# Buttons.net
KiCad netlist of a schematic drawn in Altium Designer
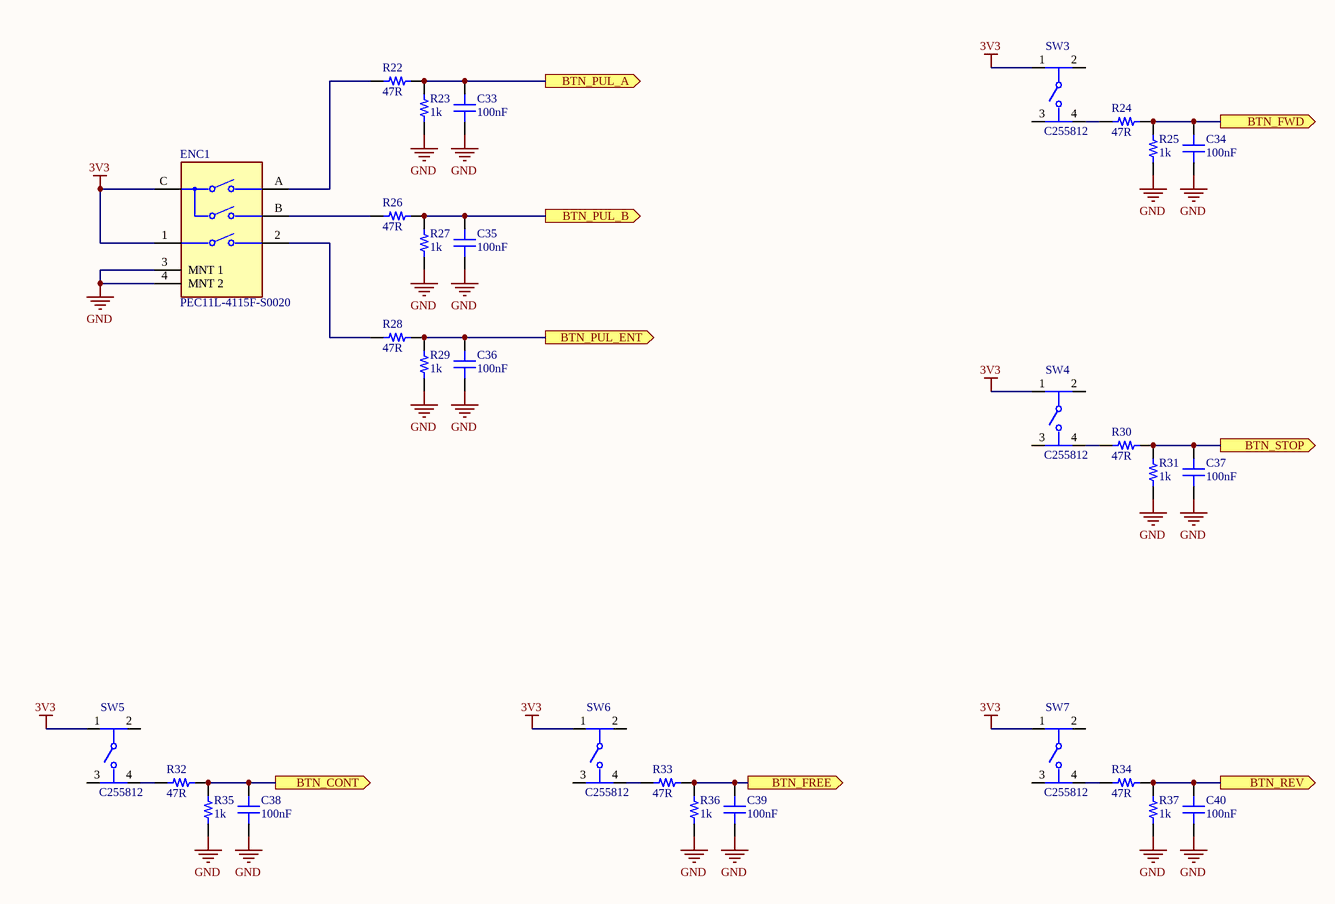
[diagram p0: Buttons.SchDoc]

(export (version "E")
  (design (tool "Eeschema 10.0.6"))
  (components
    (comp (ref "C33")
      (value "100nF")
      (footprint "CAP 0603_1608")
      (description "C14663")
      (fields
        (field (name "PART NUMBER") "250X14W223MV4T")
        (field (name "MANUFACTURER") "Johanson Dielectrics Inc.")
      )
      (libsource (lib "Celestial Altium Library - altium_library") (part "Capacitor"))
    )
    (comp (ref "C34")
      (value "100nF")
      (footprint "CAP 0603_1608")
      (description "C14663")
      (fields
        (field (name "PART NUMBER") "250X14W223MV4T")
        (field (name "MANUFACTURER") "Johanson Dielectrics Inc.")
      )
      (libsource (lib "Celestial Altium Library - altium_library") (part "Capacitor"))
    )
    (comp (ref "C35")
      (value "100nF")
      (footprint "CAP 0603_1608")
      (description "C14663")
      (fields
        (field (name "PART NUMBER") "250X14W223MV4T")
        (field (name "MANUFACTURER") "Johanson Dielectrics Inc.")
      )
      (libsource (lib "Celestial Altium Library - altium_library") (part "Capacitor"))
    )
    (comp (ref "C36")
      (value "100nF")
      (footprint "CAP 0603_1608")
      (description "C14663")
      (fields
        (field (name "PART NUMBER") "250X14W223MV4T")
        (field (name "MANUFACTURER") "Johanson Dielectrics Inc.")
      )
      (libsource (lib "Celestial Altium Library - altium_library") (part "Capacitor"))
    )
    (comp (ref "C37")
      (value "100nF")
      (footprint "CAP 0603_1608")
      (description "C14663")
      (fields
        (field (name "PART NUMBER") "250X14W223MV4T")
        (field (name "MANUFACTURER") "Johanson Dielectrics Inc.")
      )
      (libsource (lib "Celestial Altium Library - altium_library") (part "Capacitor"))
    )
    (comp (ref "C38")
      (value "100nF")
      (footprint "CAP 0603_1608")
      (description "C14663")
      (fields
        (field (name "PART NUMBER") "250X14W223MV4T")
        (field (name "MANUFACTURER") "Johanson Dielectrics Inc.")
      )
      (libsource (lib "Celestial Altium Library - altium_library") (part "Capacitor"))
    )
    (comp (ref "C39")
      (value "100nF")
      (footprint "CAP 0603_1608")
      (description "C14663")
      (fields
        (field (name "PART NUMBER") "250X14W223MV4T")
        (field (name "MANUFACTURER") "Johanson Dielectrics Inc.")
      )
      (libsource (lib "Celestial Altium Library - altium_library") (part "Capacitor"))
    )
    (comp (ref "C40")
      (value "100nF")
      (footprint "CAP 0603_1608")
      (description "C14663")
      (fields
        (field (name "PART NUMBER") "250X14W223MV4T")
        (field (name "MANUFACTURER") "Johanson Dielectrics Inc.")
      )
      (libsource (lib "Celestial Altium Library - altium_library") (part "Capacitor"))
    )
    (comp (ref "ENC1")
      (value "PEC11L-4115F-S0020")
      (footprint "FP-PEC11L-4115F-S0020-MFG")
      (description "ROTARY ENCODER MECHANICAL 20PPR")
      (libsource (lib "Altium Content Vault") (part "454af83100f22c047ab3fe85c012a7b"))
    )
    (comp (ref "R22")
      (value "47R")
      (footprint "RES 0603_1608")
      (description "RES 1% 0603")
      (fields
        (field (name "PART NUMBER") "RNCF0603DTE23K2")
        (field (name "MANUFACTURER") "Stackpole Electronics Inc")
      )
      (libsource (lib "Celestial Altium Library - altium_library") (part "Resistor"))
    )
    (comp (ref "R23")
      (value "1k")
      (footprint "RES 0603_1608")
      (description "RES 1% 0603")
      (fields
        (field (name "PART NUMBER") "RNCF0603DTE23K2")
        (field (name "MANUFACTURER") "Stackpole Electronics Inc")
      )
      (libsource (lib "Celestial Altium Library - altium_library") (part "Resistor"))
    )
    (comp (ref "R24")
      (value "47R")
      (footprint "RES 0603_1608")
      (description "RES 1% 0603")
      (fields
        (field (name "PART NUMBER") "RNCF0603DTE23K2")
        (field (name "MANUFACTURER") "Stackpole Electronics Inc")
      )
      (libsource (lib "Celestial Altium Library - altium_library") (part "Resistor"))
    )
    (comp (ref "R25")
      (value "1k")
      (footprint "RES 0603_1608")
      (description "RES 1% 0603")
      (fields
        (field (name "PART NUMBER") "RNCF0603DTE23K2")
        (field (name "MANUFACTURER") "Stackpole Electronics Inc")
      )
      (libsource (lib "Celestial Altium Library - altium_library") (part "Resistor"))
    )
    (comp (ref "R26")
      (value "47R")
      (footprint "RES 0603_1608")
      (description "RES 1% 0603")
      (fields
        (field (name "PART NUMBER") "RNCF0603DTE23K2")
        (field (name "MANUFACTURER") "Stackpole Electronics Inc")
      )
      (libsource (lib "Celestial Altium Library - altium_library") (part "Resistor"))
    )
    (comp (ref "R27")
      (value "1k")
      (footprint "RES 0603_1608")
      (description "RES 1% 0603")
      (fields
        (field (name "PART NUMBER") "RNCF0603DTE23K2")
        (field (name "MANUFACTURER") "Stackpole Electronics Inc")
      )
      (libsource (lib "Celestial Altium Library - altium_library") (part "Resistor"))
    )
    (comp (ref "R28")
      (value "47R")
      (footprint "RES 0603_1608")
      (description "RES 1% 0603")
      (fields
        (field (name "PART NUMBER") "RNCF0603DTE23K2")
        (field (name "MANUFACTURER") "Stackpole Electronics Inc")
      )
      (libsource (lib "Celestial Altium Library - altium_library") (part "Resistor"))
    )
    (comp (ref "R29")
      (value "1k")
      (footprint "RES 0603_1608")
      (description "RES 1% 0603")
      (fields
        (field (name "PART NUMBER") "RNCF0603DTE23K2")
        (field (name "MANUFACTURER") "Stackpole Electronics Inc")
      )
      (libsource (lib "Celestial Altium Library - altium_library") (part "Resistor"))
    )
    (comp (ref "R30")
      (value "47R")
      (footprint "RES 0603_1608")
      (description "RES 1% 0603")
      (fields
        (field (name "PART NUMBER") "RNCF0603DTE23K2")
        (field (name "MANUFACTURER") "Stackpole Electronics Inc")
      )
      (libsource (lib "Celestial Altium Library - altium_library") (part "Resistor"))
    )
    (comp (ref "R31")
      (value "1k")
      (footprint "RES 0603_1608")
      (description "RES 1% 0603")
      (fields
        (field (name "PART NUMBER") "RNCF0603DTE23K2")
        (field (name "MANUFACTURER") "Stackpole Electronics Inc")
      )
      (libsource (lib "Celestial Altium Library - altium_library") (part "Resistor"))
    )
    (comp (ref "R32")
      (value "47R")
      (footprint "RES 0603_1608")
      (description "RES 1% 0603")
      (fields
        (field (name "PART NUMBER") "RNCF0603DTE23K2")
        (field (name "MANUFACTURER") "Stackpole Electronics Inc")
      )
      (libsource (lib "Celestial Altium Library - altium_library") (part "Resistor"))
    )
    (comp (ref "R33")
      (value "47R")
      (footprint "RES 0603_1608")
      (description "RES 1% 0603")
      (fields
        (field (name "PART NUMBER") "RNCF0603DTE23K2")
        (field (name "MANUFACTURER") "Stackpole Electronics Inc")
      )
      (libsource (lib "Celestial Altium Library - altium_library") (part "Resistor"))
    )
    (comp (ref "R34")
      (value "47R")
      (footprint "RES 0603_1608")
      (description "RES 1% 0603")
      (fields
        (field (name "PART NUMBER") "RNCF0603DTE23K2")
        (field (name "MANUFACTURER") "Stackpole Electronics Inc")
      )
      (libsource (lib "Celestial Altium Library - altium_library") (part "Resistor"))
    )
    (comp (ref "R35")
      (value "1k")
      (footprint "RES 0603_1608")
      (description "RES 1% 0603")
      (fields
        (field (name "PART NUMBER") "RNCF0603DTE23K2")
        (field (name "MANUFACTURER") "Stackpole Electronics Inc")
      )
      (libsource (lib "Celestial Altium Library - altium_library") (part "Resistor"))
    )
    (comp (ref "R36")
      (value "1k")
      (footprint "RES 0603_1608")
      (description "RES 1% 0603")
      (fields
        (field (name "PART NUMBER") "RNCF0603DTE23K2")
        (field (name "MANUFACTURER") "Stackpole Electronics Inc")
      )
      (libsource (lib "Celestial Altium Library - altium_library") (part "Resistor"))
    )
    (comp (ref "R37")
      (value "1k")
      (footprint "RES 0603_1608")
      (description "RES 1% 0603")
      (fields
        (field (name "PART NUMBER") "RNCF0603DTE23K2")
        (field (name "MANUFACTURER") "Stackpole Electronics Inc")
      )
      (libsource (lib "Celestial Altium Library - altium_library") (part "Resistor"))
    )
    (comp (ref "SW3")
      (value "C255812")
      (footprint "FP-FSM2JSMAA-MFG")
      (description "SWITCH TACTILE SPST-NO 0.05A 24V")
      (fields
        (field (name "MANUFACTURER PART NUMBER") "FSM2JSMAA")
        (field (name "MANUFACTURER") "TE Connectivity")
      )
      (libsource (lib "Altium Content Vault") (part "b8895f3f4cefb76e1819d2863dba89b"))
    )
    (comp (ref "SW4")
      (value "C255812")
      (footprint "FP-FSM2JSMAA-MFG")
      (description "SWITCH TACTILE SPST-NO 0.05A 24V")
      (fields
        (field (name "MANUFACTURER PART NUMBER") "FSM2JSMAA")
        (field (name "MANUFACTURER") "TE Connectivity")
      )
      (libsource (lib "Altium Content Vault") (part "b8895f3f4cefb76e1819d2863dba89b"))
    )
    (comp (ref "SW5")
      (value "C255812")
      (footprint "FP-FSM2JSMAA-MFG")
      (description "SWITCH TACTILE SPST-NO 0.05A 24V")
      (fields
        (field (name "MANUFACTURER PART NUMBER") "FSM2JSMAA")
        (field (name "MANUFACTURER") "TE Connectivity")
      )
      (libsource (lib "Altium Content Vault") (part "b8895f3f4cefb76e1819d2863dba89b"))
    )
    (comp (ref "SW6")
      (value "C255812")
      (footprint "FP-FSM2JSMAA-MFG")
      (description "SWITCH TACTILE SPST-NO 0.05A 24V")
      (fields
        (field (name "MANUFACTURER PART NUMBER") "FSM2JSMAA")
        (field (name "MANUFACTURER") "TE Connectivity")
      )
      (libsource (lib "Altium Content Vault") (part "b8895f3f4cefb76e1819d2863dba89b"))
    )
    (comp (ref "SW7")
      (value "C255812")
      (footprint "FP-FSM2JSMAA-MFG")
      (description "SWITCH TACTILE SPST-NO 0.05A 24V")
      (fields
        (field (name "MANUFACTURER PART NUMBER") "FSM2JSMAA")
        (field (name "MANUFACTURER") "TE Connectivity")
      )
      (libsource (lib "Altium Content Vault") (part "b8895f3f4cefb76e1819d2863dba89b"))
    )
  )
  (nets
    (net (code "1") (name "/BTN_CONT") (class "Default")
      (node (ref "C38") (pin "1") (pinfunction "1_1") (pintype "passive"))
      (node (ref "R32") (pin "2") (pinfunction "2_2") (pintype "passive"))
      (node (ref "R35") (pin "1") (pinfunction "1_1") (pintype "passive"))
    )
    (net (code "2") (name "/BTN_FREE") (class "Default")
      (node (ref "C39") (pin "1") (pinfunction "1_1") (pintype "passive"))
      (node (ref "R33") (pin "2") (pinfunction "2_2") (pintype "passive"))
      (node (ref "R36") (pin "1") (pinfunction "1_1") (pintype "passive"))
    )
    (net (code "3") (name "/BTN_FWD") (class "Default")
      (node (ref "C34") (pin "1") (pinfunction "1_1") (pintype "passive"))
      (node (ref "R24") (pin "2") (pinfunction "2_2") (pintype "passive"))
      (node (ref "R25") (pin "1") (pinfunction "1_1") (pintype "passive"))
    )
    (net (code "4") (name "/BTN_PUL_A") (class "Default")
      (node (ref "C33") (pin "1") (pinfunction "1_1") (pintype "passive"))
      (node (ref "R22") (pin "2") (pinfunction "2_2") (pintype "passive"))
      (node (ref "R23") (pin "1") (pinfunction "1_1") (pintype "passive"))
    )
    (net (code "5") (name "/BTN_PUL_B") (class "Default")
      (node (ref "C35") (pin "1") (pinfunction "1_1") (pintype "passive"))
      (node (ref "R26") (pin "2") (pinfunction "2_2") (pintype "passive"))
      (node (ref "R27") (pin "1") (pinfunction "1_1") (pintype "passive"))
    )
    (net (code "6") (name "/BTN_PUL_ENT") (class "Default")
      (node (ref "C36") (pin "1") (pinfunction "1_1") (pintype "passive"))
      (node (ref "R28") (pin "2") (pinfunction "2_2") (pintype "passive"))
      (node (ref "R29") (pin "1") (pinfunction "1_1") (pintype "passive"))
    )
    (net (code "7") (name "/BTN_REV") (class "Default")
      (node (ref "C40") (pin "1") (pinfunction "1_1") (pintype "passive"))
      (node (ref "R34") (pin "2") (pinfunction "2_2") (pintype "passive"))
      (node (ref "R37") (pin "1") (pinfunction "1_1") (pintype "passive"))
    )
    (net (code "8") (name "/BTN_STOP") (class "Default")
      (node (ref "C37") (pin "1") (pinfunction "1_1") (pintype "passive"))
      (node (ref "R30") (pin "2") (pinfunction "2_2") (pintype "passive"))
      (node (ref "R31") (pin "1") (pinfunction "1_1") (pintype "passive"))
    )
    (net (code "9") (name "3V3") (class "Default")
      (node (ref "ENC1") (pin "1") (pinfunction "1_1") (pintype "passive"))
      (node (ref "ENC1") (pin "C") (pinfunction "COMMON_C") (pintype "passive"))
      (node (ref "SW3") (pin "1") (pinfunction "1_1") (pintype "passive"))
      (node (ref "SW4") (pin "1") (pinfunction "1_1") (pintype "passive"))
      (node (ref "SW5") (pin "1") (pinfunction "1_1") (pintype "passive"))
      (node (ref "SW6") (pin "1") (pinfunction "1_1") (pintype "passive"))
      (node (ref "SW7") (pin "1") (pinfunction "1_1") (pintype "passive"))
    )
    (net (code "10") (name "GND") (class "Default")
      (node (ref "C33") (pin "2") (pinfunction "2_2") (pintype "passive"))
      (node (ref "C34") (pin "2") (pinfunction "2_2") (pintype "passive"))
      (node (ref "C35") (pin "2") (pinfunction "2_2") (pintype "passive"))
      (node (ref "C36") (pin "2") (pinfunction "2_2") (pintype "passive"))
      (node (ref "C37") (pin "2") (pinfunction "2_2") (pintype "passive"))
      (node (ref "C38") (pin "2") (pinfunction "2_2") (pintype "passive"))
      (node (ref "C39") (pin "2") (pinfunction "2_2") (pintype "passive"))
      (node (ref "C40") (pin "2") (pinfunction "2_2") (pintype "passive"))
      (node (ref "ENC1") (pin "3") (pinfunction "MNT_1_3") (pintype "passive"))
      (node (ref "ENC1") (pin "4") (pinfunction "MNT_2_4") (pintype "passive"))
      (node (ref "R23") (pin "2") (pinfunction "2_2") (pintype "passive"))
      (node (ref "R25") (pin "2") (pinfunction "2_2") (pintype "passive"))
      (node (ref "R27") (pin "2") (pinfunction "2_2") (pintype "passive"))
      (node (ref "R29") (pin "2") (pinfunction "2_2") (pintype "passive"))
      (node (ref "R31") (pin "2") (pinfunction "2_2") (pintype "passive"))
      (node (ref "R35") (pin "2") (pinfunction "2_2") (pintype "passive"))
      (node (ref "R36") (pin "2") (pinfunction "2_2") (pintype "passive"))
      (node (ref "R37") (pin "2") (pinfunction "2_2") (pintype "passive"))
    )
    (net (code "11") (name "Net-(ENC1-CHANNEL_A)") (class "Default")
      (node (ref "ENC1") (pin "A") (pinfunction "CHANNEL_A_A") (pintype "passive"))
      (node (ref "R22") (pin "1") (pinfunction "1_1") (pintype "passive"))
    )
    (net (code "12") (name "Net-(ENC1-CHANNEL_B)") (class "Default")
      (node (ref "ENC1") (pin "B") (pinfunction "CHANNEL_B_B") (pintype "passive"))
      (node (ref "R26") (pin "1") (pinfunction "1_1") (pintype "passive"))
    )
    (net (code "13") (name "Net-(ENC1-Pad2)") (class "Default")
      (node (ref "ENC1") (pin "2") (pinfunction "2_2") (pintype "passive"))
      (node (ref "R28") (pin "1") (pinfunction "1_1") (pintype "passive"))
    )
    (net (code "14") (name "Net-(R24-Pad1)") (class "Default")
      (node (ref "R24") (pin "1") (pinfunction "1_1") (pintype "passive"))
      (node (ref "SW3") (pin "4") (pinfunction "4_4") (pintype "passive"))
    )
    (net (code "15") (name "Net-(R30-Pad1)") (class "Default")
      (node (ref "R30") (pin "1") (pinfunction "1_1") (pintype "passive"))
      (node (ref "SW4") (pin "4") (pinfunction "4_4") (pintype "passive"))
    )
    (net (code "16") (name "Net-(R32-Pad1)") (class "Default")
      (node (ref "R32") (pin "1") (pinfunction "1_1") (pintype "passive"))
      (node (ref "SW5") (pin "4") (pinfunction "4_4") (pintype "passive"))
    )
    (net (code "17") (name "Net-(R33-Pad1)") (class "Default")
      (node (ref "R33") (pin "1") (pinfunction "1_1") (pintype "passive"))
      (node (ref "SW6") (pin "4") (pinfunction "4_4") (pintype "passive"))
    )
    (net (code "18") (name "Net-(R34-Pad1)") (class "Default")
      (node (ref "R34") (pin "1") (pinfunction "1_1") (pintype "passive"))
      (node (ref "SW7") (pin "4") (pinfunction "4_4") (pintype "passive"))
    )
    (net (code "19") (name "unconnected-(SW3-Pad2)") (class "Default")
      (node (ref "SW3") (pin "2") (pinfunction "2_2") (pintype "passive"))
    )
    (net (code "20") (name "unconnected-(SW3-Pad3)") (class "Default")
      (node (ref "SW3") (pin "3") (pinfunction "3_3") (pintype "passive"))
    )
    (net (code "21") (name "unconnected-(SW4-Pad2)") (class "Default")
      (node (ref "SW4") (pin "2") (pinfunction "2_2") (pintype "passive"))
    )
    (net (code "22") (name "unconnected-(SW4-Pad3)") (class "Default")
      (node (ref "SW4") (pin "3") (pinfunction "3_3") (pintype "passive"))
    )
    (net (code "23") (name "unconnected-(SW5-Pad2)") (class "Default")
      (node (ref "SW5") (pin "2") (pinfunction "2_2") (pintype "passive"))
    )
    (net (code "24") (name "unconnected-(SW5-Pad3)") (class "Default")
      (node (ref "SW5") (pin "3") (pinfunction "3_3") (pintype "passive"))
    )
    (net (code "25") (name "unconnected-(SW6-Pad2)") (class "Default")
      (node (ref "SW6") (pin "2") (pinfunction "2_2") (pintype "passive"))
    )
    (net (code "26") (name "unconnected-(SW6-Pad3)") (class "Default")
      (node (ref "SW6") (pin "3") (pinfunction "3_3") (pintype "passive"))
    )
    (net (code "27") (name "unconnected-(SW7-Pad2)") (class "Default")
      (node (ref "SW7") (pin "2") (pinfunction "2_2") (pintype "passive"))
    )
    (net (code "28") (name "unconnected-(SW7-Pad3)") (class "Default")
      (node (ref "SW7") (pin "3") (pinfunction "3_3") (pintype "passive"))
    )
  )
)
